# Sheet1.net
KiCad netlist of a schematic drawn in Altium Designer
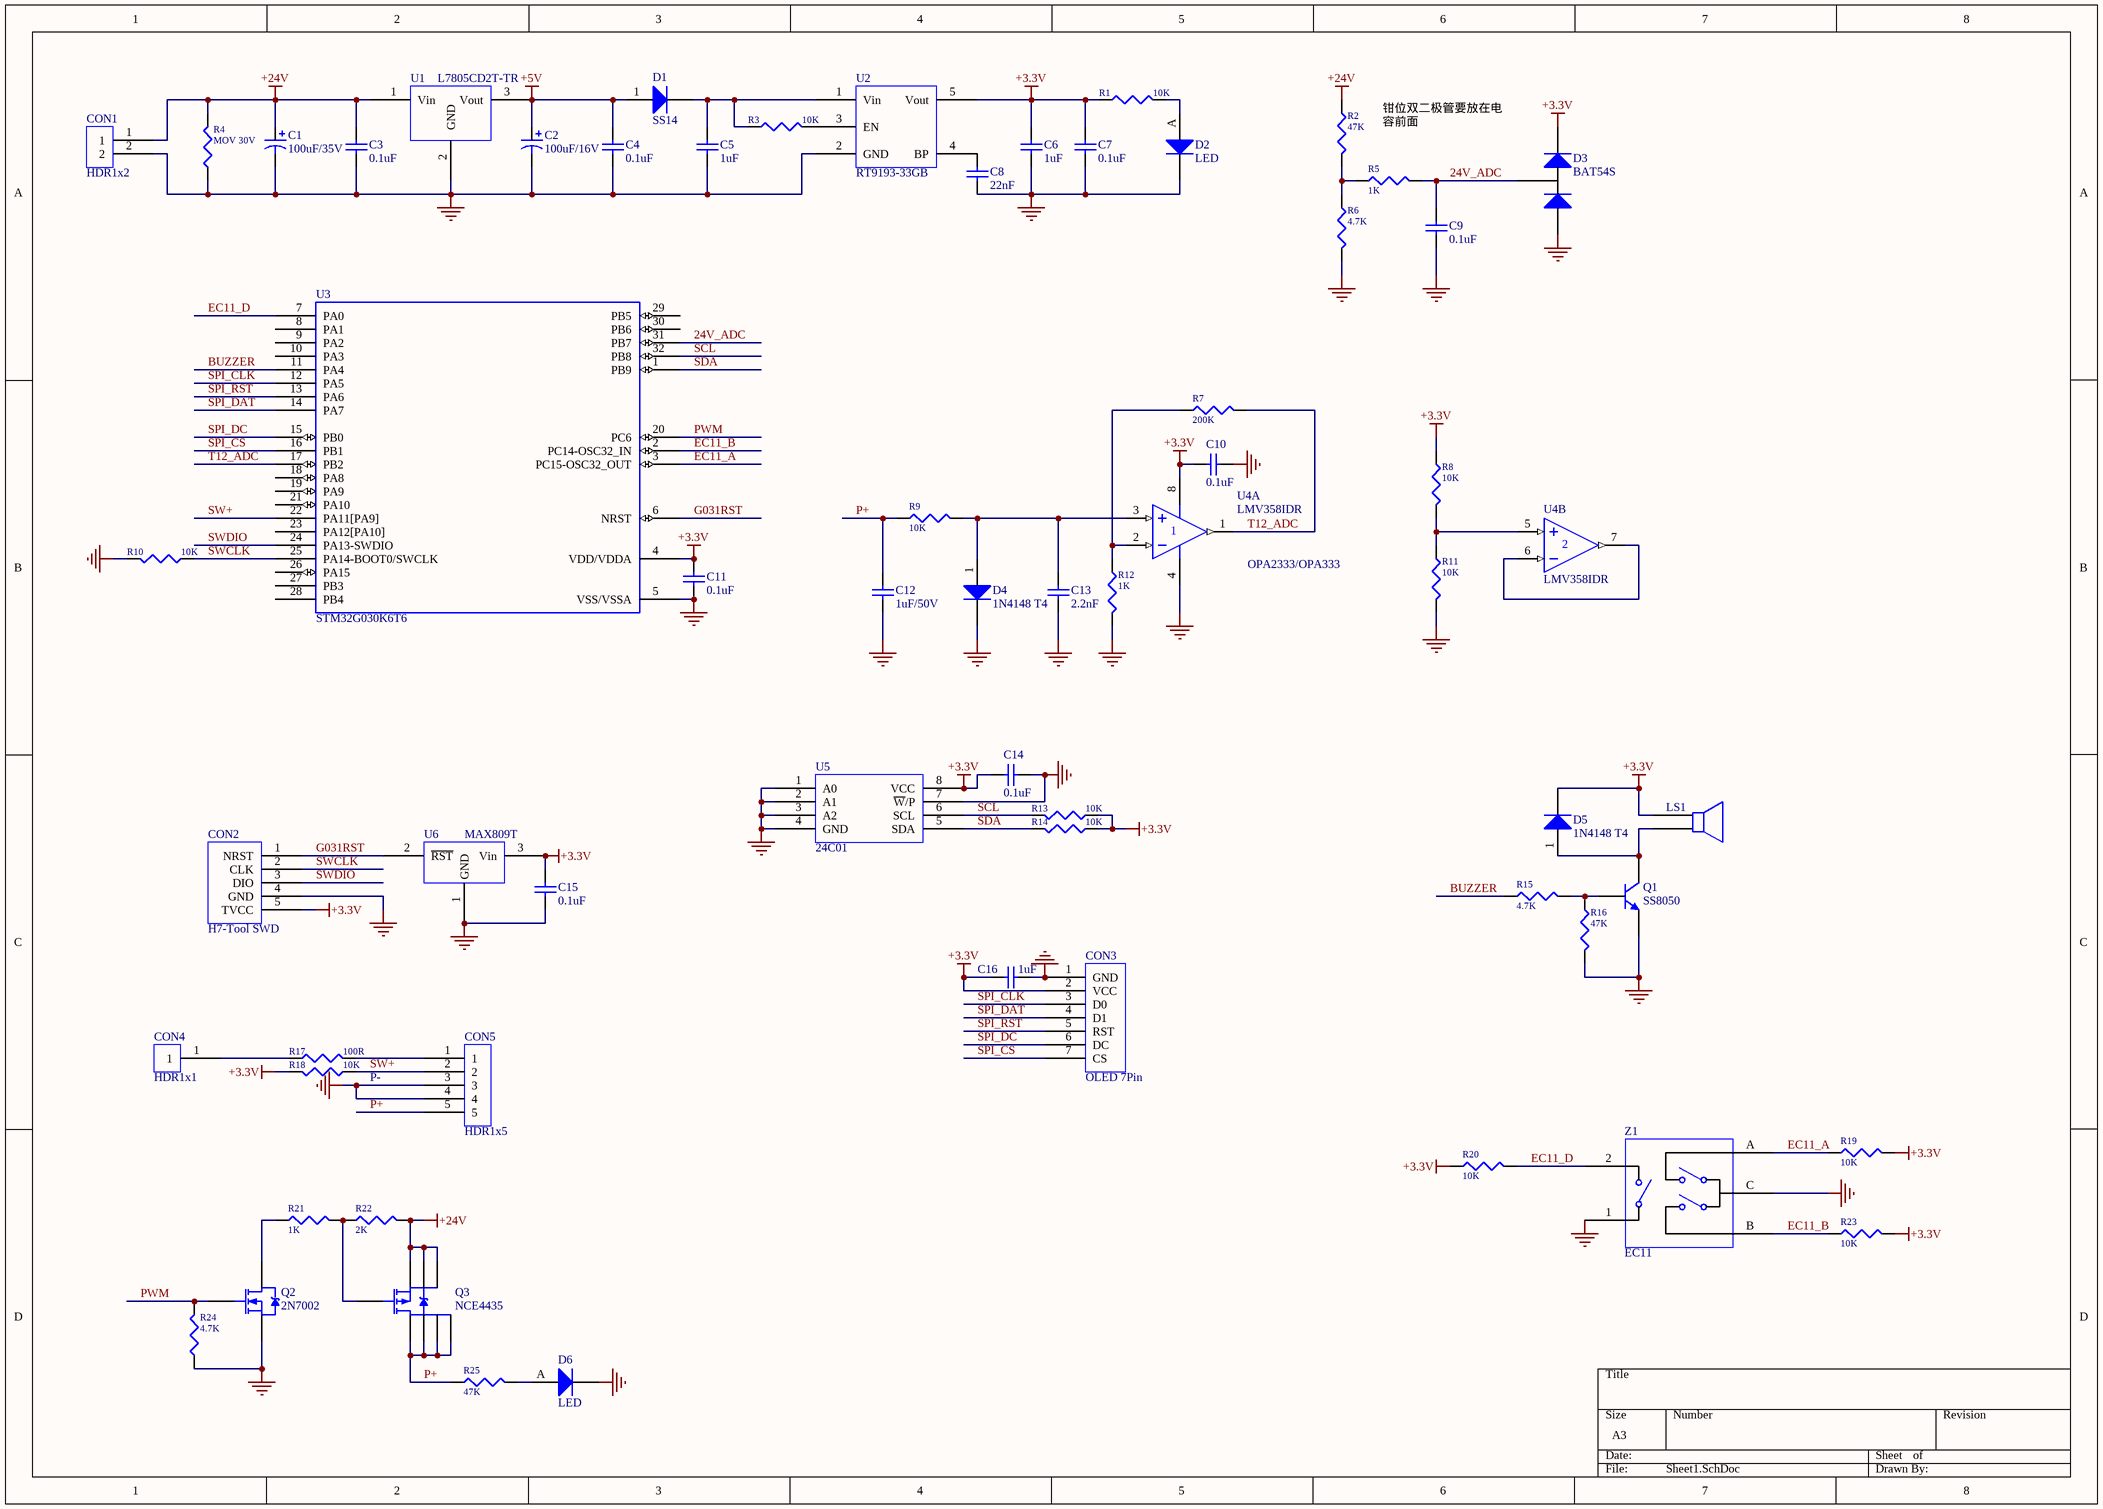
[diagram p0: Sheet1.SchDoc]

(export (version "E")
  (design (tool "Eeschema 10.0.6"))
  (components
    (comp (ref "C1")
      (value "100uF/35V")
      (footprint "CAP-SMD_BD6.3-L6.6-W6.6-FD")
      (description "Polarized Capacitor (Radial)")
      (fields (field (name "Comment") "Cap Pol1") (field (name "PUBLISHER") "Altium Limited"))
      (libsource (lib "Miscellaneous Devices") (part "Cap Pol1"))
    )
    (comp (ref "C2")
      (value "100uF/16V")
      (footprint "CAP-SMD_BD6.3-L6.6-W6.6-FD")
      (description "Polarized Capacitor (Radial)")
      (fields (field (name "Comment") "Cap Pol1") (field (name "PUBLISHER") "Altium Limited"))
      (libsource (lib "Miscellaneous Devices") (part "Cap Pol1"))
    )
    (comp (ref "C3")
      (value "0.1uF")
      (footprint "0603_C")
      (description "贴片电容")
      (libsource (lib "Miscellaneous Devices LC") (part "0603 100nF (104) 10% 50V"))
    )
    (comp (ref "C4")
      (value "0.1uF")
      (footprint "0603_C")
      (description "贴片电容")
      (libsource (lib "Miscellaneous Devices LC") (part "0603 100nF (104) 10% 50V"))
    )
    (comp (ref "C5")
      (value "1uF")
      (footprint "0603_C")
      (description "贴片电容")
      (libsource (lib "Miscellaneous Devices LC") (part "0603 100nF (104) 10% 50V"))
    )
    (comp (ref "C6")
      (value "1uF")
      (footprint "0603_C")
      (description "贴片电容")
      (libsource (lib "Miscellaneous Devices LC") (part "0603 100nF (104) 10% 50V"))
    )
    (comp (ref "C7")
      (value "0.1uF")
      (footprint "0603_C")
      (description "贴片电容")
      (libsource (lib "Miscellaneous Devices LC") (part "0603 100nF (104) 10% 50V"))
    )
    (comp (ref "C8")
      (value "22nF")
      (footprint "0603_C")
      (description "贴片电容")
      (libsource (lib "Miscellaneous Devices LC") (part "0603 100nF (104) 10% 50V"))
    )
    (comp (ref "C9")
      (value "0.1uF")
      (footprint "0603_C")
      (description "贴片电容")
      (libsource (lib "Miscellaneous Devices LC") (part "0603 100nF (104) 10% 50V"))
    )
    (comp (ref "C10")
      (value "0.1uF")
      (footprint "0603_C")
      (description "贴片电容")
      (libsource (lib "Miscellaneous Devices LC") (part "0603 100nF (104) 10% 50V"))
    )
    (comp (ref "C11")
      (value "0.1uF")
      (footprint "0603_C")
      (description "贴片电容")
      (libsource (lib "Miscellaneous Devices LC") (part "0603 100nF (104) 10% 50V"))
    )
    (comp (ref "C12")
      (value "1uF/50V")
      (footprint "0603_C")
      (description "贴片电容")
      (libsource (lib "Miscellaneous Devices LC") (part "0603 100nF (104) 10% 50V"))
    )
    (comp (ref "C13")
      (value "2.2nF")
      (footprint "0603_C")
      (description "贴片电容")
      (libsource (lib "Miscellaneous Devices LC") (part "0603 100nF (104) 10% 50V"))
    )
    (comp (ref "C14")
      (value "0.1uF")
      (footprint "0603_C")
      (description "贴片电容")
      (libsource (lib "Miscellaneous Devices LC") (part "0603 100nF (104) 10% 50V"))
    )
    (comp (ref "C15")
      (value "0.1uF")
      (footprint "0603_C")
      (description "贴片电容")
      (libsource (lib "Miscellaneous Devices LC") (part "0603 100nF (104) 10% 50V"))
    )
    (comp (ref "C16")
      (value "1uF")
      (footprint "0603_C")
      (description "贴片电容")
      (libsource (lib "Miscellaneous Devices LC") (part "0603 100nF (104) 10% 50V"))
    )
    (comp (ref "CON1") (value "HDR1x2") (footprint "HDR2.54-LI-2p") (libsource (lib "原理图库") (part "HDR1x2")))
    (comp (ref "CON2")
      (value "H7-Tool SWD")
      (footprint "hdr1x5")
      (libsource (lib "原理图库") (part "H7-Tool SWD"))
    )
    (comp (ref "CON3")
      (value "OLED 7Pin")
      (footprint "0.96 OLED SPI")
      (libsource (lib "原理图库") (part "OLED 7Pin"))
    )
    (comp (ref "CON4") (value "HDR1x1") (footprint "HDR2.54-LI-1P") (libsource (lib "原理图库") (part "HDR1x1")))
    (comp (ref "CON5") (value "HDR1x5") (footprint "T12_SOCKET") (libsource (lib "原理图库") (part "HDR1x5")))
    (comp (ref "D1")
      (value "SS14")
      (footprint "SMA(DO-214AC)_S1")
      (description "二极管")
      (libsource (lib "") (part "Diode_1"))
    )
    (comp (ref "D2")
      (value "LED")
      (footprint "0603_LED_S1")
      (description "二极管")
      (libsource (lib "Schlib1") (part "Diode"))
    )
    (comp (ref "D3")
      (value "BAT54S")
      (footprint "SOT-23(SOT-23-3)")
      (description "二极管")
      (libsource (lib "原理图库") (part "BAT54S"))
    )
    (comp (ref "D4")
      (value "1N4148 T4")
      (footprint "SOD-123_MARK")
      (description "二极管")
      (libsource (lib "") (part "Diode_1"))
    )
    (comp (ref "D5")
      (value "1N4148 T4")
      (footprint "SOD-123_MARK")
      (description "二极管")
      (libsource (lib "") (part "Diode_1"))
    )
    (comp (ref "D6")
      (value "LED")
      (footprint "0603_LED_S1")
      (description "二极管")
      (libsource (lib "Schlib1") (part "Diode"))
    )
    (comp (ref "LS1")
      (value "GSC8525RA-16R2700")
      (footprint "BUZ-SMD_L5.0-W5.5-P4.60")
      (fields (field (name "MANUFACTURER") "INGHAi"))
      (libsource (lib "*") (part "SPEAKER"))
    )
    (comp (ref "Q1")
      (value "SS8050")
      (footprint "SOT-23(SOT-23-3)")
      (description "NPN General Purpose Amplifier")
      (libsource (lib "原理图库") (part "SS8050"))
    )
    (comp (ref "Q2")
      (value "2N7002")
      (footprint "SOT-23(SOT-23-3)")
      (description "N-Channel Power MOSFET")
      (fields (field (name "PUBLISHER") "Altium Limited"))
      (libsource (lib "Schlib1") (part "AO3416"))
    )
    (comp (ref "Q3")
      (value "NCE4435")
      (footprint "SOP-8_150mil")
      (description "P-CH, 30V -13A 5.5mR")
      (libsource (lib "Schlib1") (part "TPC8107"))
    )
    (comp (ref "R1")
      (value "10K")
      (footprint "0603_R")
      (description "Resistor")
      (libsource (lib "*") (part "RES"))
    )
    (comp (ref "R2")
      (value "47K")
      (footprint "0603_R")
      (description "Resistor")
      (libsource (lib "*") (part "RES"))
    )
    (comp (ref "R3")
      (value "10K")
      (footprint "0603_R")
      (description "Resistor")
      (libsource (lib "*") (part "RES"))
    )
    (comp (ref "R4")
      (value "MOV 30V")
      (footprint "0805_R")
      (description "Resistor")
      (libsource (lib "*") (part "RES"))
    )
    (comp (ref "R5")
      (value "1K")
      (footprint "0603_R")
      (description "Resistor")
      (libsource (lib "*") (part "RES"))
    )
    (comp (ref "R6")
      (value "4.7K")
      (footprint "0603_R")
      (description "Resistor")
      (libsource (lib "*") (part "RES"))
    )
    (comp (ref "R7")
      (value "200K")
      (footprint "0603_R")
      (description "Resistor")
      (libsource (lib "*") (part "RES"))
    )
    (comp (ref "R8")
      (value "10K")
      (footprint "0603_R")
      (description "Resistor")
      (libsource (lib "*") (part "RES"))
    )
    (comp (ref "R9")
      (value "10K")
      (footprint "0603_R")
      (description "Resistor")
      (libsource (lib "*") (part "RES"))
    )
    (comp (ref "R10")
      (value "10K")
      (footprint "0603_R")
      (description "Resistor")
      (libsource (lib "*") (part "RES"))
    )
    (comp (ref "R11")
      (value "10K")
      (footprint "0603_R")
      (description "Resistor")
      (libsource (lib "*") (part "RES"))
    )
    (comp (ref "R12")
      (value "1K")
      (footprint "0603_R")
      (description "Resistor")
      (libsource (lib "*") (part "RES"))
    )
    (comp (ref "R13")
      (value "10K")
      (footprint "0603_R")
      (description "Resistor")
      (libsource (lib "*") (part "RES"))
    )
    (comp (ref "R14")
      (value "10K")
      (footprint "0603_R")
      (description "Resistor")
      (libsource (lib "*") (part "RES"))
    )
    (comp (ref "R15")
      (value "4.7K")
      (footprint "0603_R")
      (description "Resistor")
      (libsource (lib "*") (part "RES"))
    )
    (comp (ref "R16")
      (value "47K")
      (footprint "0603_R")
      (description "Resistor")
      (libsource (lib "*") (part "RES"))
    )
    (comp (ref "R17")
      (value "100R")
      (footprint "1206_R")
      (description "Resistor")
      (libsource (lib "*") (part "RES"))
    )
    (comp (ref "R18")
      (value "10K")
      (footprint "0603_R")
      (description "Resistor")
      (libsource (lib "*") (part "RES"))
    )
    (comp (ref "R19")
      (value "10K")
      (footprint "0603_R")
      (description "Resistor")
      (libsource (lib "*") (part "RES"))
    )
    (comp (ref "R20")
      (value "10K")
      (footprint "0603_R")
      (description "Resistor")
      (libsource (lib "*") (part "RES"))
    )
    (comp (ref "R21")
      (value "1K")
      (footprint "0603_R")
      (description "Resistor")
      (libsource (lib "*") (part "RES"))
    )
    (comp (ref "R22")
      (value "2K")
      (footprint "0603_R")
      (description "Resistor")
      (libsource (lib "*") (part "RES"))
    )
    (comp (ref "R23")
      (value "10K")
      (footprint "0603_R")
      (description "Resistor")
      (libsource (lib "*") (part "RES"))
    )
    (comp (ref "R24")
      (value "4.7K")
      (footprint "0603_R")
      (description "Resistor")
      (libsource (lib "*") (part "RES"))
    )
    (comp (ref "R25")
      (value "47K")
      (footprint "0603_R")
      (description "Resistor")
      (libsource (lib "*") (part "RES"))
    )
    (comp (ref "U1") (value "L7805CD2T-TR") (footprint "TO-263-2") (libsource (lib "原理图库") (part "78M05")))
    (comp (ref "U2")
      (value "RT9193-33GB")
      (footprint "SOT-23-5")
      (libsource (lib "Schlib1") (part "RT9193-33GB"))
    )
    (comp (ref "U3")
      (value "STM32G030K6T6")
      (footprint "LQFP-32_7x7x08P")
      (description "No Description Available")
      (libsource (lib "Schlib1") (part "STM32G030K6T6"))
    )
    (comp (ref "U4")
      (value "LMV358IDR")
      (footprint "Miscellaneous Devices LC:SOP-8_150mil")
      (description "通用运放")
      (libsource (lib "原理图库") (part "LM358"))
    )
    (comp (ref "U5") (value "24C01") (footprint "SOP-8_150mil") (libsource (lib "原理图库") (part "24LC64")))
    (comp (ref "U6")
      (value "MAX809T")
      (footprint "SOT-23(SOT-23-3)")
      (description "3.08v")
      (libsource (lib "Schlib1") (part "MAX809T"))
    )
    (comp (ref "Z1") (value "EC11") (footprint "EC11-B") (libsource (lib "原理图库") (part "EC11")))
  )
  (nets
    (net (code "1") (name "+3.3V") (class "Default")
      (node (ref "C10") (pin "1") (pinfunction "1_1") (pintype "passive"))
      (node (ref "C11") (pin "2") (pinfunction "2_2") (pintype "passive"))
      (node (ref "C14") (pin "2") (pinfunction "2_2") (pintype "passive"))
      (node (ref "C15") (pin "1") (pinfunction "1_1") (pintype "passive"))
      (node (ref "C16") (pin "1") (pinfunction "1_1") (pintype "passive"))
      (node (ref "C6") (pin "2") (pinfunction "2_2") (pintype "passive"))
      (node (ref "C7") (pin "2") (pinfunction "2_2") (pintype "passive"))
      (node (ref "CON2") (pin "5") (pinfunction "TVCC_5") (pintype "passive"))
      (node (ref "CON3") (pin "2") (pinfunction "VCC_2") (pintype "passive"))
      (node (ref "D3") (pin "2") (pinfunction "2_2") (pintype "passive"))
      (node (ref "D5") (pin "2") (pinfunction "K_2") (pintype "passive"))
      (node (ref "LS1") (pin "1") (pinfunction "1_1") (pintype "passive"))
      (node (ref "R1") (pin "2") (pinfunction "BOT_2") (pintype "passive"))
      (node (ref "R13") (pin "1") (pinfunction "TOP_1") (pintype "passive"))
      (node (ref "R14") (pin "1") (pinfunction "TOP_1") (pintype "passive"))
      (node (ref "R18") (pin "2") (pinfunction "BOT_2") (pintype "passive"))
      (node (ref "R19") (pin "2") (pinfunction "BOT_2") (pintype "passive"))
      (node (ref "R20") (pin "1") (pinfunction "TOP_1") (pintype "passive"))
      (node (ref "R23") (pin "2") (pinfunction "BOT_2") (pintype "passive"))
      (node (ref "R8") (pin "1") (pinfunction "TOP_1") (pintype "passive"))
      (node (ref "U2") (pin "5") (pinfunction "Vout_5") (pintype "passive"))
      (node (ref "U3") (pin "4") (pinfunction "VDD/VDDA_4") (pintype "power_in"))
      (node (ref "U4") (pin "8") (pinfunction "8_8") (pintype "passive"))
      (node (ref "U5") (pin "8") (pinfunction "VCC_8") (pintype "passive"))
      (node (ref "U6") (pin "3") (pinfunction "Vin_3") (pintype "passive"))
    )
    (net (code "2") (name "+5V") (class "Default")
      (node (ref "C2") (pin "1") (pinfunction "1_1") (pintype "passive"))
      (node (ref "C4") (pin "2") (pinfunction "2_2") (pintype "passive"))
      (node (ref "D1") (pin "1") (pinfunction "A_1") (pintype "passive"))
      (node (ref "U1") (pin "3") (pinfunction "Vout_3") (pintype "passive"))
    )
    (net (code "3") (name "+24V") (class "Default")
      (node (ref "C1") (pin "1") (pinfunction "1_1") (pintype "passive"))
      (node (ref "C3") (pin "2") (pinfunction "2_2") (pintype "passive"))
      (node (ref "CON1") (pin "1") (pinfunction "1_1") (pintype "passive"))
      (node (ref "Q3") (pin "1") (pinfunction "S_1") (pintype "passive"))
      (node (ref "Q3") (pin "2") (pinfunction "S_2") (pintype "passive"))
      (node (ref "Q3") (pin "3") (pinfunction "S_3") (pintype "passive"))
      (node (ref "R2") (pin "1") (pinfunction "TOP_1") (pintype "passive"))
      (node (ref "R22") (pin "2") (pinfunction "BOT_2") (pintype "passive"))
      (node (ref "R4") (pin "1") (pinfunction "TOP_1") (pintype "passive"))
      (node (ref "U1") (pin "1") (pinfunction "Vin_1") (pintype "passive"))
    )
    (net (code "4") (name "/24V_ADC") (class "Default")
      (node (ref "C9") (pin "2") (pinfunction "2_2") (pintype "passive"))
      (node (ref "D3") (pin "3") (pinfunction "3_3") (pintype "passive"))
      (node (ref "R5") (pin "2") (pinfunction "BOT_2") (pintype "passive"))
      (node (ref "U3") (pin "31") (pinfunction "PB7_31") (pintype "bidirectional"))
    )
    (net (code "5") (name "/BUZZER") (class "Default")
      (node (ref "R15") (pin "1") (pinfunction "TOP_1") (pintype "passive"))
      (node (ref "U3") (pin "11") (pinfunction "PA4_11") (pintype "passive"))
    )
    (net (code "6") (name "/EC11_A") (class "Default")
      (node (ref "R19") (pin "1") (pinfunction "TOP_1") (pintype "passive"))
      (node (ref "U3") (pin "3") (pinfunction "PC15-OSC32_OUT_3") (pintype "bidirectional"))
      (node (ref "Z1") (pin "A") (pinfunction "A_A") (pintype "passive"))
    )
    (net (code "7") (name "/EC11_B") (class "Default")
      (node (ref "R23") (pin "1") (pinfunction "TOP_1") (pintype "passive"))
      (node (ref "U3") (pin "2") (pinfunction "PC14-OSC32_IN_2") (pintype "bidirectional"))
      (node (ref "Z1") (pin "B") (pinfunction "B_B") (pintype "passive"))
    )
    (net (code "8") (name "/EC11_D") (class "Default")
      (node (ref "R20") (pin "2") (pinfunction "BOT_2") (pintype "passive"))
      (node (ref "U3") (pin "7") (pinfunction "PA0_7") (pintype "passive"))
      (node (ref "Z1") (pin "2") (pinfunction "D_2") (pintype "passive"))
    )
    (net (code "9") (name "/G031RST") (class "Default")
      (node (ref "CON2") (pin "1") (pinfunction "NRST_1") (pintype "passive"))
      (node (ref "U3") (pin "6") (pinfunction "NRST_6") (pintype "bidirectional"))
      (node (ref "U6") (pin "2") (pinfunction "~{RST}_2") (pintype "passive"))
    )
    (net (code "10") (name "/P+") (class "Default")
      (node (ref "C12") (pin "2") (pinfunction "2_2") (pintype "passive"))
      (node (ref "CON5") (pin "5") (pinfunction "5_5") (pintype "passive"))
      (node (ref "Q3") (pin "5") (pinfunction "D_5") (pintype "passive"))
      (node (ref "Q3") (pin "6") (pinfunction "D_6") (pintype "passive"))
      (node (ref "Q3") (pin "7") (pinfunction "D_7") (pintype "passive"))
      (node (ref "Q3") (pin "8") (pinfunction "D_8") (pintype "passive"))
      (node (ref "R25") (pin "2") (pinfunction "BOT_2") (pintype "passive"))
      (node (ref "R9") (pin "1") (pinfunction "TOP_1") (pintype "passive"))
    )
    (net (code "11") (name "/PWM") (class "Default")
      (node (ref "Q2") (pin "1") (pinfunction "G_1") (pintype "passive"))
      (node (ref "R24") (pin "2") (pinfunction "BOT_2") (pintype "passive"))
      (node (ref "U3") (pin "20") (pinfunction "PC6_20") (pintype "bidirectional"))
    )
    (net (code "12") (name "/SCL") (class "Default")
      (node (ref "R13") (pin "2") (pinfunction "BOT_2") (pintype "passive"))
      (node (ref "U3") (pin "32") (pinfunction "PB8_32") (pintype "bidirectional"))
      (node (ref "U5") (pin "6") (pinfunction "SCL_6") (pintype "passive"))
    )
    (net (code "13") (name "/SDA") (class "Default")
      (node (ref "R14") (pin "2") (pinfunction "BOT_2") (pintype "passive"))
      (node (ref "U3") (pin "1") (pinfunction "PB9_1") (pintype "bidirectional"))
      (node (ref "U5") (pin "5") (pinfunction "SDA_5") (pintype "passive"))
    )
    (net (code "14") (name "/SPI_CLK") (class "Default")
      (node (ref "CON3") (pin "3") (pinfunction "D0_3") (pintype "passive"))
      (node (ref "U3") (pin "12") (pinfunction "PA5_12") (pintype "passive"))
    )
    (net (code "15") (name "/SPI_CS") (class "Default")
      (node (ref "CON3") (pin "7") (pinfunction "CS_7") (pintype "passive"))
      (node (ref "U3") (pin "16") (pinfunction "PB1_16") (pintype "passive"))
    )
    (net (code "16") (name "/SPI_DAT") (class "Default")
      (node (ref "CON3") (pin "4") (pinfunction "D1_4") (pintype "passive"))
      (node (ref "U3") (pin "14") (pinfunction "PA7_14") (pintype "passive"))
    )
    (net (code "17") (name "/SPI_DC") (class "Default")
      (node (ref "CON3") (pin "6") (pinfunction "DC_6") (pintype "passive"))
      (node (ref "U3") (pin "15") (pinfunction "PB0_15") (pintype "bidirectional"))
    )
    (net (code "18") (name "/SPI_RST") (class "Default")
      (node (ref "CON3") (pin "5") (pinfunction "RST_5") (pintype "passive"))
      (node (ref "U3") (pin "13") (pinfunction "PA6_13") (pintype "passive"))
    )
    (net (code "19") (name "/SW+") (class "Default")
      (node (ref "CON5") (pin "2") (pinfunction "2_2") (pintype "passive"))
      (node (ref "R18") (pin "1") (pinfunction "TOP_1") (pintype "passive"))
      (node (ref "U3") (pin "22") (pinfunction "PA11[PA9]_22") (pintype "passive"))
    )
    (net (code "20") (name "/SWCLK") (class "Default")
      (node (ref "CON2") (pin "2") (pinfunction "CLK_2") (pintype "passive"))
      (node (ref "R10") (pin "1") (pinfunction "TOP_1") (pintype "passive"))
      (node (ref "U3") (pin "25") (pinfunction "PA14-BOOT0/SWCLK_25") (pintype "passive"))
    )
    (net (code "21") (name "/SWDIO") (class "Default")
      (node (ref "CON2") (pin "3") (pinfunction "DIO_3") (pintype "passive"))
      (node (ref "U3") (pin "24") (pinfunction "PA13-SWDIO_24") (pintype "passive"))
    )
    (net (code "22") (name "/T12_ADC") (class "Default")
      (node (ref "R7") (pin "2") (pinfunction "BOT_2") (pintype "passive"))
      (node (ref "U3") (pin "17") (pinfunction "PB2_17") (pintype "bidirectional"))
      (node (ref "U4") (pin "1") (pinfunction "OUT_1") (pintype "output"))
    )
    (net (code "23") (name "GND") (class "Default")
      (node (ref "C1") (pin "2") (pinfunction "2_2") (pintype "passive"))
      (node (ref "C10") (pin "2") (pinfunction "2_2") (pintype "passive"))
      (node (ref "C11") (pin "1") (pinfunction "1_1") (pintype "passive"))
      (node (ref "C12") (pin "1") (pinfunction "1_1") (pintype "passive"))
      (node (ref "C13") (pin "1") (pinfunction "1_1") (pintype "passive"))
      (node (ref "C14") (pin "1") (pinfunction "1_1") (pintype "passive"))
      (node (ref "C15") (pin "2") (pinfunction "2_2") (pintype "passive"))
      (node (ref "C16") (pin "2") (pinfunction "2_2") (pintype "passive"))
      (node (ref "C2") (pin "2") (pinfunction "2_2") (pintype "passive"))
      (node (ref "C3") (pin "1") (pinfunction "1_1") (pintype "passive"))
      (node (ref "C4") (pin "1") (pinfunction "1_1") (pintype "passive"))
      (node (ref "C5") (pin "1") (pinfunction "1_1") (pintype "passive"))
      (node (ref "C6") (pin "1") (pinfunction "1_1") (pintype "passive"))
      (node (ref "C7") (pin "1") (pinfunction "1_1") (pintype "passive"))
      (node (ref "C8") (pin "1") (pinfunction "1_1") (pintype "passive"))
      (node (ref "C9") (pin "1") (pinfunction "1_1") (pintype "passive"))
      (node (ref "CON1") (pin "2") (pinfunction "2_2") (pintype "passive"))
      (node (ref "CON2") (pin "4") (pinfunction "GND_4") (pintype "passive"))
      (node (ref "CON3") (pin "1") (pinfunction "GND_1") (pintype "passive"))
      (node (ref "CON5") (pin "3") (pinfunction "3_3") (pintype "passive"))
      (node (ref "CON5") (pin "4") (pinfunction "4_4") (pintype "passive"))
      (node (ref "D2") (pin "K") (pinfunction "K_K") (pintype "passive"))
      (node (ref "D3") (pin "1") (pinfunction "1_1") (pintype "passive"))
      (node (ref "D4") (pin "2") (pinfunction "K_2") (pintype "passive"))
      (node (ref "D6") (pin "K") (pinfunction "K_K") (pintype "passive"))
      (node (ref "Q1") (pin "2") (pinfunction "E_2") (pintype "passive"))
      (node (ref "Q2") (pin "2") (pinfunction "S_2") (pintype "passive"))
      (node (ref "R10") (pin "2") (pinfunction "BOT_2") (pintype "passive"))
      (node (ref "R11") (pin "2") (pinfunction "BOT_2") (pintype "passive"))
      (node (ref "R12") (pin "2") (pinfunction "BOT_2") (pintype "passive"))
      (node (ref "R16") (pin "2") (pinfunction "BOT_2") (pintype "passive"))
      (node (ref "R24") (pin "1") (pinfunction "TOP_1") (pintype "passive"))
      (node (ref "R4") (pin "2") (pinfunction "BOT_2") (pintype "passive"))
      (node (ref "R6") (pin "2") (pinfunction "BOT_2") (pintype "passive"))
      (node (ref "U1") (pin "2") (pinfunction "GND_2") (pintype "passive"))
      (node (ref "U2") (pin "2") (pinfunction "GND_2") (pintype "passive"))
      (node (ref "U3") (pin "5") (pinfunction "VSS/VSSA_5") (pintype "power_in"))
      (node (ref "U4") (pin "4") (pinfunction "4_4") (pintype "passive"))
      (node (ref "U5") (pin "1") (pinfunction "A0_1") (pintype "passive"))
      (node (ref "U5") (pin "2") (pinfunction "A1_2") (pintype "passive"))
      (node (ref "U5") (pin "3") (pinfunction "A2_3") (pintype "passive"))
      (node (ref "U5") (pin "4") (pinfunction "GND_4") (pintype "passive"))
      (node (ref "U5") (pin "7") (pinfunction "~{W}/P_7") (pintype "passive"))
      (node (ref "U6") (pin "1") (pinfunction "GND_1") (pintype "passive"))
      (node (ref "Z1") (pin "1") (pinfunction "E_1") (pintype "passive"))
      (node (ref "Z1") (pin "C") (pinfunction "C_C") (pintype "passive"))
    )
    (net (code "24") (name "Net-(D1-K)") (class "Default")
      (node (ref "C5") (pin "2") (pinfunction "2_2") (pintype "passive"))
      (node (ref "D1") (pin "2") (pinfunction "K_2") (pintype "passive"))
      (node (ref "R3") (pin "2") (pinfunction "BOT_2") (pintype "passive"))
      (node (ref "U2") (pin "1") (pinfunction "Vin_1") (pintype "passive"))
    )
    (net (code "25") (name "Net-(D4-A)") (class "Default")
      (node (ref "C13") (pin "2") (pinfunction "2_2") (pintype "passive"))
      (node (ref "D4") (pin "1") (pinfunction "A_1") (pintype "passive"))
      (node (ref "R9") (pin "2") (pinfunction "BOT_2") (pintype "passive"))
      (node (ref "U4") (pin "3") (pinfunction "IN+_3") (pintype "input"))
    )
    (net (code "26") (name "Net-(D5-A)") (class "Default")
      (node (ref "D5") (pin "1") (pinfunction "A_1") (pintype "passive"))
      (node (ref "LS1") (pin "2") (pinfunction "2_2") (pintype "passive"))
      (node (ref "Q1") (pin "3") (pinfunction "C_3") (pintype "passive"))
    )
    (net (code "27") (name "Net-(Q1-B)") (class "Default")
      (node (ref "Q1") (pin "1") (pinfunction "B_1") (pintype "passive"))
      (node (ref "R15") (pin "2") (pinfunction "BOT_2") (pintype "passive"))
      (node (ref "R16") (pin "1") (pinfunction "TOP_1") (pintype "passive"))
    )
    (net (code "28") (name "Net-(Q2-D)") (class "Default")
      (node (ref "Q2") (pin "3") (pinfunction "D_3") (pintype "passive"))
      (node (ref "R21") (pin "1") (pinfunction "TOP_1") (pintype "passive"))
    )
    (net (code "29") (name "Net-(Q3-G)") (class "Default")
      (node (ref "Q3") (pin "4") (pinfunction "G_4") (pintype "passive"))
      (node (ref "R21") (pin "2") (pinfunction "BOT_2") (pintype "passive"))
      (node (ref "R22") (pin "1") (pinfunction "TOP_1") (pintype "passive"))
    )
    (net (code "30") (name "Net-(R1-TOP)") (class "Default")
      (node (ref "D2") (pin "A") (pinfunction "A_A") (pintype "passive"))
      (node (ref "R1") (pin "1") (pinfunction "TOP_1") (pintype "passive"))
    )
    (net (code "31") (name "Net-(R2-BOT)") (class "Default")
      (node (ref "R2") (pin "2") (pinfunction "BOT_2") (pintype "passive"))
      (node (ref "R5") (pin "1") (pinfunction "TOP_1") (pintype "passive"))
      (node (ref "R6") (pin "1") (pinfunction "TOP_1") (pintype "passive"))
    )
    (net (code "32") (name "Net-(R3-TOP)") (class "Default")
      (node (ref "R3") (pin "1") (pinfunction "TOP_1") (pintype "passive"))
      (node (ref "U2") (pin "3") (pinfunction "EN_3") (pintype "passive"))
    )
    (net (code "33") (name "Net-(R11-TOP)") (class "Default")
      (node (ref "R11") (pin "1") (pinfunction "TOP_1") (pintype "passive"))
      (node (ref "R8") (pin "2") (pinfunction "BOT_2") (pintype "passive"))
      (node (ref "U4") (pin "5") (pinfunction "IN+_5") (pintype "input"))
    )
    (net (code "34") (name "Net-(R12-TOP)") (class "Default")
      (node (ref "R12") (pin "1") (pinfunction "TOP_1") (pintype "passive"))
      (node (ref "R7") (pin "1") (pinfunction "TOP_1") (pintype "passive"))
      (node (ref "U4") (pin "2") (pinfunction "IN-_2") (pintype "input"))
    )
    (net (code "35") (name "Net-(R17-BOT)") (class "Default")
      (node (ref "CON5") (pin "1") (pinfunction "1_1") (pintype "passive"))
      (node (ref "R17") (pin "2") (pinfunction "BOT_2") (pintype "passive"))
    )
    (net (code "36") (name "Net-(R17-TOP)") (class "Default")
      (node (ref "CON4") (pin "1") (pinfunction "1_1") (pintype "passive"))
      (node (ref "R17") (pin "1") (pinfunction "TOP_1") (pintype "passive"))
    )
    (net (code "37") (name "Net-(R25-TOP)") (class "Default")
      (node (ref "D6") (pin "A") (pinfunction "A_A") (pintype "passive"))
      (node (ref "R25") (pin "1") (pinfunction "TOP_1") (pintype "passive"))
    )
    (net (code "38") (name "Net-(U2-BP)") (class "Default")
      (node (ref "C8") (pin "2") (pinfunction "2_2") (pintype "passive"))
      (node (ref "U2") (pin "4") (pinfunction "BP_4") (pintype "passive"))
    )
    (net (code "39") (name "Net-(U4B-IN-)") (class "Default")
      (node (ref "U4") (pin "6") (pinfunction "IN-_6") (pintype "input"))
      (node (ref "U4") (pin "7") (pinfunction "OUT_7") (pintype "output"))
    )
    (net (code "40") (name "unconnected-(U3-PA1-Pad8)") (class "Default")
      (node (ref "U3") (pin "8") (pinfunction "PA1_8") (pintype "passive"))
    )
    (net (code "41") (name "unconnected-(U3-PA2-Pad9)") (class "Default")
      (node (ref "U3") (pin "9") (pinfunction "PA2_9") (pintype "passive"))
    )
    (net (code "42") (name "unconnected-(U3-PA3-Pad10)") (class "Default")
      (node (ref "U3") (pin "10") (pinfunction "PA3_10") (pintype "passive"))
    )
    (net (code "43") (name "unconnected-(U3-PA8-Pad18)") (class "Default")
      (node (ref "U3") (pin "18") (pinfunction "PA8_18") (pintype "bidirectional"))
    )
    (net (code "44") (name "unconnected-(U3-PA9-Pad19)") (class "Default")
      (node (ref "U3") (pin "19") (pinfunction "PA9_19") (pintype "bidirectional"))
    )
    (net (code "45") (name "unconnected-(U3-PA10-Pad21)") (class "Default")
      (node (ref "U3") (pin "21") (pinfunction "PA10_21") (pintype "bidirectional"))
    )
    (net (code "46") (name "unconnected-(U3-PA12[PA10]-Pad23)") (class "Default")
      (node (ref "U3") (pin "23") (pinfunction "PA12[PA10]_23") (pintype "passive"))
    )
    (net (code "47") (name "unconnected-(U3-PA15-Pad26)") (class "Default")
      (node (ref "U3") (pin "26") (pinfunction "PA15_26") (pintype "bidirectional"))
    )
    (net (code "48") (name "unconnected-(U3-PB3-Pad27)") (class "Default")
      (node (ref "U3") (pin "27") (pinfunction "PB3_27") (pintype "passive"))
    )
    (net (code "49") (name "unconnected-(U3-PB4-Pad28)") (class "Default")
      (node (ref "U3") (pin "28") (pinfunction "PB4_28") (pintype "passive"))
    )
    (net (code "50") (name "unconnected-(U3-PB5-Pad29)") (class "Default")
      (node (ref "U3") (pin "29") (pinfunction "PB5_29") (pintype "bidirectional"))
    )
    (net (code "51") (name "unconnected-(U3-PB6-Pad30)") (class "Default")
      (node (ref "U3") (pin "30") (pinfunction "PB6_30") (pintype "bidirectional"))
    )
  )
)
